# SCH_Cart_Main_PCB_2023-04-13.net
KiCad netlist of a schematic drawn in EasyEDA
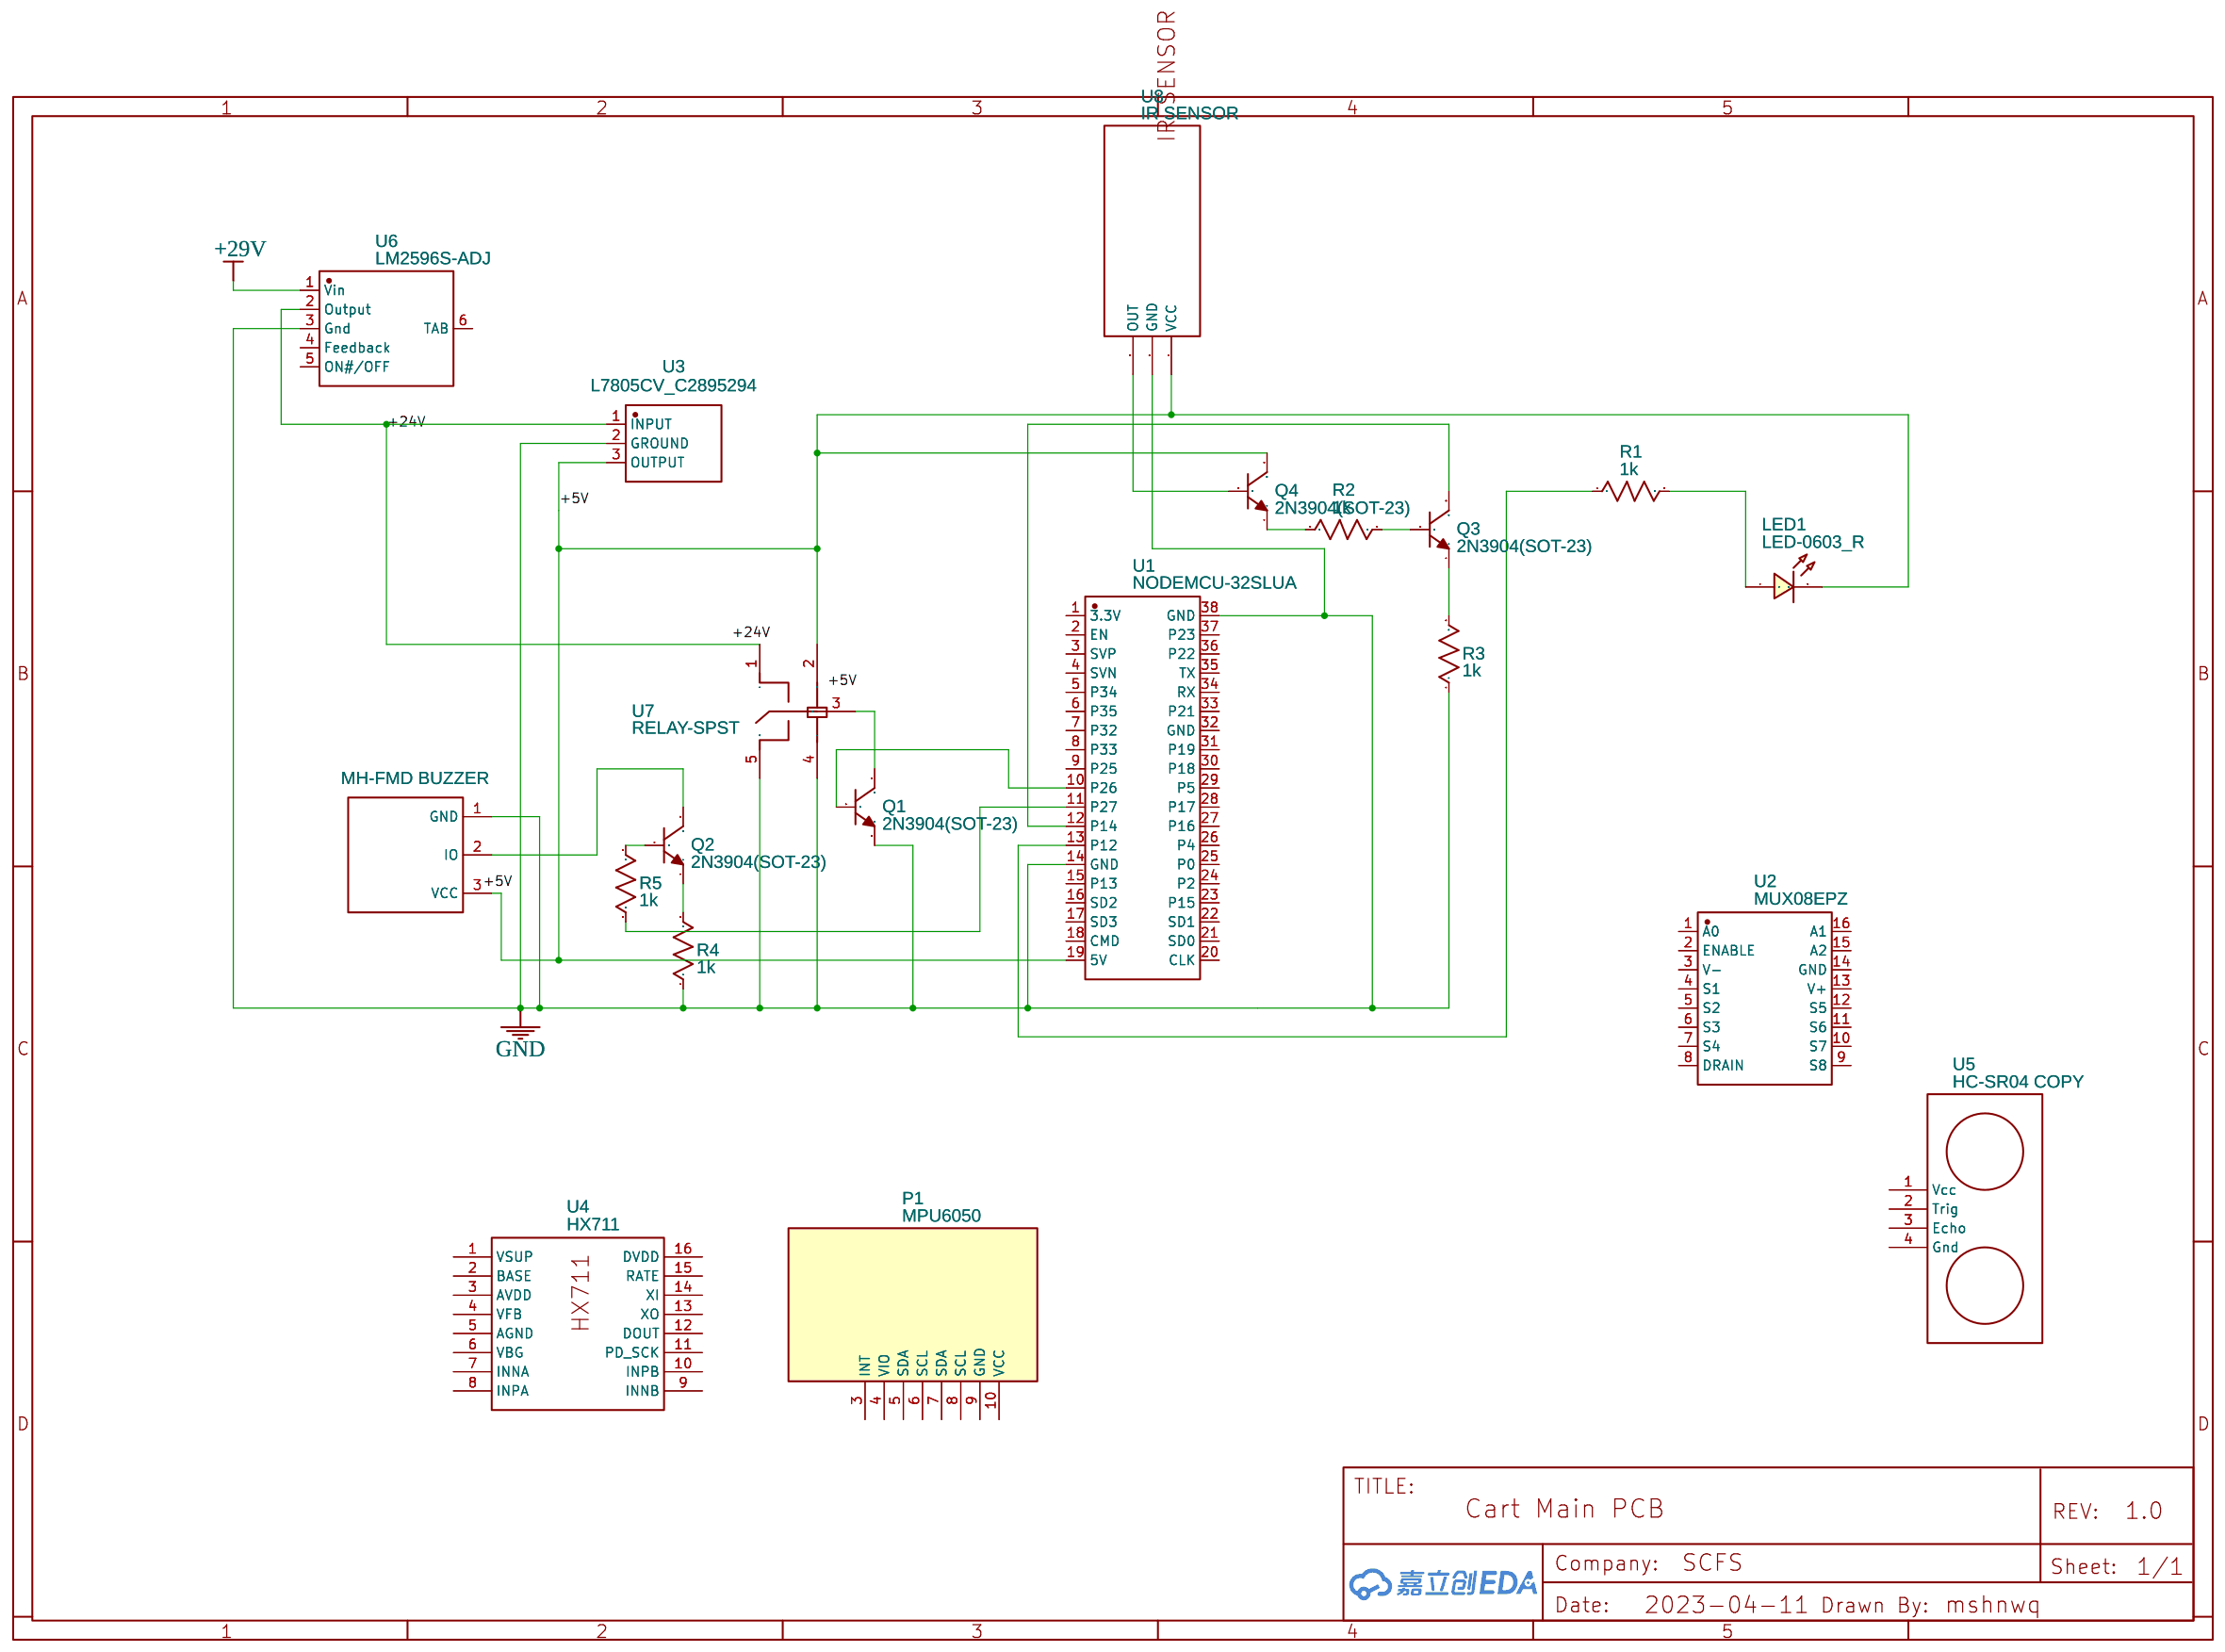
[diagram p0: schematic sheet]

(export (version "E")
  (design (tool "Eeschema 10.0.6"))
  (components
    (comp (ref "GND")
      (value "MH-FMD BUZZER")
      (fields (field (name "BOM_Supplier Part") "MH-FMD"))
      (libsource (lib "") (part "MH-FMD BUZZER"))
    )
    (comp (ref "LED1")
      (value "LED-0603_R")
      (fields
        (field (name "BOM_Manufacturer Part") "19-217/R6C-AL1M2VY/3T")
        (field (name "BOM_Supplier Part") "C72044")
      )
      (libsource (lib "") (part "LED-0603_R"))
    )
    (comp (ref "P1") (value "MPU6050") (libsource (lib "") (part "MPU6050")))
    (comp (ref "Q1")
      (value "2N3904(SOT-23)")
      (fields
        (field (name "BOM_Manufacturer Part") "2n3904S-RTK/PS")
        (field (name "BOM_Supplier Part") "C18536")
      )
      (libsource (lib "") (part "2N3904(SOT-23)"))
    )
    (comp (ref "Q2")
      (value "2N3904(SOT-23)")
      (fields
        (field (name "BOM_Manufacturer Part") "2n3904S-RTK/PS")
        (field (name "BOM_Supplier Part") "C18536")
      )
      (libsource (lib "") (part "2N3904(SOT-23)"))
    )
    (comp (ref "Q3")
      (value "2N3904(SOT-23)")
      (fields
        (field (name "BOM_Manufacturer Part") "2n3904S-RTK/PS")
        (field (name "BOM_Supplier Part") "C18536")
      )
      (libsource (lib "") (part "2N3904(SOT-23)"))
    )
    (comp (ref "Q4")
      (value "2N3904(SOT-23)")
      (fields
        (field (name "BOM_Manufacturer Part") "2n3904S-RTK/PS")
        (field (name "BOM_Supplier Part") "C18536")
      )
      (libsource (lib "") (part "2N3904(SOT-23)"))
    )
    (comp (ref "R1") (value "1k") (libsource (lib "") (part "R_0603_US_1")))
    (comp (ref "R2") (value "1k") (libsource (lib "") (part "R_0603_US_1")))
    (comp (ref "R3") (value "1k") (libsource (lib "") (part "R_0603_US")))
    (comp (ref "R4") (value "1k") (libsource (lib "") (part "R_0603_US")))
    (comp (ref "R5") (value "1k") (libsource (lib "") (part "R_0603_US_2")))
    (comp (ref "U1")
      (value "NODEMCU-32SLUA")
      (fields
        (field (name "BOM_Manufacturer Part") "NodeMCU-32SLua")
        (field (name "BOM_Supplier Part") "C111436")
      )
      (libsource (lib "") (part "NODEMCU-32SLUA"))
    )
    (comp (ref "U2")
      (value "MUX08EPZ")
      (fields (field (name "BOM_Supplier Part") "C690856"))
      (libsource (lib "") (part "MUX08EPZ"))
    )
    (comp (ref "U3")
      (value "L7805CV_C2895294")
      (fields
        (field (name "BOM_Manufacturer Part") "L7805CV带散热器")
        (field (name "BOM_Supplier Part") "C2895294")
      )
      (libsource (lib "") (part "L7805CV_C2895294"))
    )
    (comp (ref "U4")
      (value "HX711")
      (fields (field (name "BOM_Supplier Part") "C43656"))
      (libsource (lib "") (part "HX711"))
    )
    (comp (ref "U5") (value "HC-SR04 COPY") (libsource (lib "") (part "HC-SR04 COPY")))
    (comp (ref "U6")
      (value "LM2596S-ADJ")
      (fields (field (name "BOM_Supplier Part") "C347423"))
      (libsource (lib "") (part "LM2596S-ADJ"))
    )
    (comp (ref "U7")
      (value "RELAY-SPST")
      (fields
        (field (name "BOM_Manufacturer Part") "Relay-SPST")
        (field (name "BOM_Supplier Part") "C2941249")
      )
      (libsource (lib "") (part "RELAY-SPST"))
    )
    (comp (ref "U8") (value "IR SENSOR") (libsource (lib "") (part "MH-Sensor-Series Line Sensor")))
  )
  (nets
    (net (code "1") (name "+29V") (class "Default")
      (node (ref "U6") (pin "1") (pinfunction "Vin_1") (pintype "unspecified"))
    )
    (net (code "2") (name "/+5V") (class "Default")
      (node (ref "GND") (pin "3") (pinfunction "VCC_3") (pintype "unspecified"))
      (node (ref "LED1") (pin "2") (pinfunction "2_2") (pintype "unspecified"))
      (node (ref "Q4") (pin "3") (pinfunction "C_3") (pintype "input"))
      (node (ref "U1") (pin "19") (pinfunction "5V_19") (pintype "unspecified"))
      (node (ref "U3") (pin "3") (pinfunction "OUTPUT_3") (pintype "unspecified"))
      (node (ref "U7") (pin "2") (pinfunction "2_2") (pintype "unspecified"))
      (node (ref "U8") (pin "4") (pinfunction "VCC_4") (pintype "unspecified"))
    )
    (net (code "3") (name "/+24V") (class "Default")
      (node (ref "U3") (pin "1") (pinfunction "INPUT_1") (pintype "unspecified"))
      (node (ref "U6") (pin "2") (pinfunction "Output_2") (pintype "unspecified"))
      (node (ref "U7") (pin "1") (pinfunction "1_1") (pintype "unspecified"))
    )
    (net (code "4") (name "GND") (class "Default")
      (node (ref "GND") (pin "1") (pinfunction "GND_1") (pintype "unspecified"))
      (node (ref "Q1") (pin "1") (pinfunction "E_1") (pintype "input"))
      (node (ref "R3") (pin "1") (pinfunction "1_1") (pintype "unspecified"))
      (node (ref "R4") (pin "1") (pinfunction "1_1") (pintype "unspecified"))
      (node (ref "U1") (pin "14") (pinfunction "GND_14") (pintype "unspecified"))
      (node (ref "U1") (pin "38") (pinfunction "GND_38") (pintype "unspecified"))
      (node (ref "U3") (pin "2") (pinfunction "GROUND_2") (pintype "unspecified"))
      (node (ref "U6") (pin "3") (pinfunction "Gnd_3") (pintype "unspecified"))
      (node (ref "U7") (pin "4") (pinfunction "4_4") (pintype "unspecified"))
      (node (ref "U7") (pin "5") (pinfunction "5_5") (pintype "unspecified"))
      (node (ref "U8") (pin "3") (pinfunction "GND_3") (pintype "unspecified"))
    )
    (net (code "5") (name "Net-(GND-IO)") (class "Default")
      (node (ref "GND") (pin "2") (pinfunction "IO_2") (pintype "unspecified"))
      (node (ref "Q2") (pin "3") (pinfunction "C_3") (pintype "input"))
    )
    (net (code "6") (name "Net-(LED1-Pad1)") (class "Default")
      (node (ref "LED1") (pin "1") (pinfunction "1_1") (pintype "unspecified"))
      (node (ref "R1") (pin "2") (pinfunction "2_2") (pintype "unspecified"))
    )
    (net (code "7") (name "Net-(Q1-B)") (class "Default")
      (node (ref "Q1") (pin "2") (pinfunction "B_2") (pintype "input"))
      (node (ref "U1") (pin "10") (pinfunction "P26_10") (pintype "unspecified"))
    )
    (net (code "8") (name "Net-(Q1-C)") (class "Default")
      (node (ref "Q1") (pin "3") (pinfunction "C_3") (pintype "input"))
      (node (ref "U7") (pin "3") (pinfunction "3_3") (pintype "unspecified"))
    )
    (net (code "9") (name "Net-(Q2-B)") (class "Default")
      (node (ref "Q2") (pin "2") (pinfunction "B_2") (pintype "input"))
      (node (ref "R5") (pin "1") (pinfunction "1_1") (pintype "unspecified"))
    )
    (net (code "10") (name "Net-(Q2-E)") (class "Default")
      (node (ref "Q2") (pin "1") (pinfunction "E_1") (pintype "input"))
      (node (ref "R4") (pin "2") (pinfunction "2_2") (pintype "unspecified"))
    )
    (net (code "11") (name "Net-(Q3-B)") (class "Default")
      (node (ref "Q3") (pin "2") (pinfunction "B_2") (pintype "input"))
      (node (ref "R2") (pin "2") (pinfunction "2_2") (pintype "unspecified"))
    )
    (net (code "12") (name "Net-(Q3-C)") (class "Default")
      (node (ref "Q3") (pin "3") (pinfunction "C_3") (pintype "input"))
      (node (ref "U1") (pin "12") (pinfunction "P14_12") (pintype "unspecified"))
    )
    (net (code "13") (name "Net-(Q3-E)") (class "Default")
      (node (ref "Q3") (pin "1") (pinfunction "E_1") (pintype "input"))
      (node (ref "R3") (pin "2") (pinfunction "2_2") (pintype "unspecified"))
    )
    (net (code "14") (name "Net-(Q4-B)") (class "Default")
      (node (ref "Q4") (pin "2") (pinfunction "B_2") (pintype "input"))
      (node (ref "U8") (pin "2") (pinfunction "OUT_2") (pintype "unspecified"))
    )
    (net (code "15") (name "Net-(Q4-E)") (class "Default")
      (node (ref "Q4") (pin "1") (pinfunction "E_1") (pintype "input"))
      (node (ref "R2") (pin "1") (pinfunction "1_1") (pintype "unspecified"))
    )
    (net (code "16") (name "Net-(U1-P12)") (class "Default")
      (node (ref "R1") (pin "1") (pinfunction "1_1") (pintype "unspecified"))
      (node (ref "U1") (pin "13") (pinfunction "P12_13") (pintype "unspecified"))
    )
    (net (code "17") (name "Net-(U1-P27)") (class "Default")
      (node (ref "R5") (pin "2") (pinfunction "2_2") (pintype "unspecified"))
      (node (ref "U1") (pin "11") (pinfunction "P27_11") (pintype "unspecified"))
    )
    (net (code "18") (name "unconnected-(P1-GND-Pad9)") (class "Default")
      (node (ref "P1") (pin "9") (pinfunction "GND_9") (pintype "unspecified"))
    )
    (net (code "19") (name "unconnected-(P1-INT-Pad3)") (class "Default")
      (node (ref "P1") (pin "3") (pinfunction "INT_3") (pintype "unspecified"))
    )
    (net (code "20") (name "unconnected-(P1-SCL-Pad6)") (class "Default")
      (node (ref "P1") (pin "6") (pinfunction "SCL_6") (pintype "unspecified"))
    )
    (net (code "21") (name "unconnected-(P1-SCL-Pad8)") (class "Default")
      (node (ref "P1") (pin "8") (pinfunction "SCL_8") (pintype "unspecified"))
    )
    (net (code "22") (name "unconnected-(P1-SDA-Pad5)") (class "Default")
      (node (ref "P1") (pin "5") (pinfunction "SDA_5") (pintype "unspecified"))
    )
    (net (code "23") (name "unconnected-(P1-SDA-Pad7)") (class "Default")
      (node (ref "P1") (pin "7") (pinfunction "SDA_7") (pintype "unspecified"))
    )
    (net (code "24") (name "unconnected-(P1-VCC-Pad10)") (class "Default")
      (node (ref "P1") (pin "10") (pinfunction "VCC_10") (pintype "unspecified"))
    )
    (net (code "25") (name "unconnected-(P1-VIO-Pad4)") (class "Default")
      (node (ref "P1") (pin "4") (pinfunction "VIO_4") (pintype "unspecified"))
    )
    (net (code "26") (name "unconnected-(U1-3.3V-Pad1)") (class "Default")
      (node (ref "U1") (pin "1") (pinfunction "3.3V_1") (pintype "unspecified"))
    )
    (net (code "27") (name "unconnected-(U1-CLK-Pad20)") (class "Default")
      (node (ref "U1") (pin "20") (pinfunction "CLK_20") (pintype "unspecified"))
    )
    (net (code "28") (name "unconnected-(U1-CMD-Pad18)") (class "Default")
      (node (ref "U1") (pin "18") (pinfunction "CMD_18") (pintype "unspecified"))
    )
    (net (code "29") (name "unconnected-(U1-EN-Pad2)") (class "Default")
      (node (ref "U1") (pin "2") (pinfunction "EN_2") (pintype "unspecified"))
    )
    (net (code "30") (name "unconnected-(U1-GND-Pad32)") (class "Default")
      (node (ref "U1") (pin "32") (pinfunction "GND_32") (pintype "unspecified"))
    )
    (net (code "31") (name "unconnected-(U1-P0-Pad25)") (class "Default")
      (node (ref "U1") (pin "25") (pinfunction "P0_25") (pintype "unspecified"))
    )
    (net (code "32") (name "unconnected-(U1-P2-Pad24)") (class "Default")
      (node (ref "U1") (pin "24") (pinfunction "P2_24") (pintype "unspecified"))
    )
    (net (code "33") (name "unconnected-(U1-P4-Pad26)") (class "Default")
      (node (ref "U1") (pin "26") (pinfunction "P4_26") (pintype "unspecified"))
    )
    (net (code "34") (name "unconnected-(U1-P5-Pad29)") (class "Default")
      (node (ref "U1") (pin "29") (pinfunction "P5_29") (pintype "unspecified"))
    )
    (net (code "35") (name "unconnected-(U1-P13-Pad15)") (class "Default")
      (node (ref "U1") (pin "15") (pinfunction "P13_15") (pintype "unspecified"))
    )
    (net (code "36") (name "unconnected-(U1-P15-Pad23)") (class "Default")
      (node (ref "U1") (pin "23") (pinfunction "P15_23") (pintype "unspecified"))
    )
    (net (code "37") (name "unconnected-(U1-P16-Pad27)") (class "Default")
      (node (ref "U1") (pin "27") (pinfunction "P16_27") (pintype "unspecified"))
    )
    (net (code "38") (name "unconnected-(U1-P17-Pad28)") (class "Default")
      (node (ref "U1") (pin "28") (pinfunction "P17_28") (pintype "unspecified"))
    )
    (net (code "39") (name "unconnected-(U1-P18-Pad30)") (class "Default")
      (node (ref "U1") (pin "30") (pinfunction "P18_30") (pintype "unspecified"))
    )
    (net (code "40") (name "unconnected-(U1-P19-Pad31)") (class "Default")
      (node (ref "U1") (pin "31") (pinfunction "P19_31") (pintype "unspecified"))
    )
    (net (code "41") (name "unconnected-(U1-P21-Pad33)") (class "Default")
      (node (ref "U1") (pin "33") (pinfunction "P21_33") (pintype "unspecified"))
    )
    (net (code "42") (name "unconnected-(U1-P22-Pad36)") (class "Default")
      (node (ref "U1") (pin "36") (pinfunction "P22_36") (pintype "unspecified"))
    )
    (net (code "43") (name "unconnected-(U1-P23-Pad37)") (class "Default")
      (node (ref "U1") (pin "37") (pinfunction "P23_37") (pintype "unspecified"))
    )
    (net (code "44") (name "unconnected-(U1-P25-Pad9)") (class "Default")
      (node (ref "U1") (pin "9") (pinfunction "P25_9") (pintype "unspecified"))
    )
    (net (code "45") (name "unconnected-(U1-P32-Pad7)") (class "Default")
      (node (ref "U1") (pin "7") (pinfunction "P32_7") (pintype "unspecified"))
    )
    (net (code "46") (name "unconnected-(U1-P33-Pad8)") (class "Default")
      (node (ref "U1") (pin "8") (pinfunction "P33_8") (pintype "unspecified"))
    )
    (net (code "47") (name "unconnected-(U1-P34-Pad5)") (class "Default")
      (node (ref "U1") (pin "5") (pinfunction "P34_5") (pintype "unspecified"))
    )
    (net (code "48") (name "unconnected-(U1-P35-Pad6)") (class "Default")
      (node (ref "U1") (pin "6") (pinfunction "P35_6") (pintype "unspecified"))
    )
    (net (code "49") (name "unconnected-(U1-RX-Pad34)") (class "Default")
      (node (ref "U1") (pin "34") (pinfunction "RX_34") (pintype "unspecified"))
    )
    (net (code "50") (name "unconnected-(U1-SD0-Pad21)") (class "Default")
      (node (ref "U1") (pin "21") (pinfunction "SD0_21") (pintype "unspecified"))
    )
    (net (code "51") (name "unconnected-(U1-SD1-Pad22)") (class "Default")
      (node (ref "U1") (pin "22") (pinfunction "SD1_22") (pintype "unspecified"))
    )
    (net (code "52") (name "unconnected-(U1-SD2-Pad16)") (class "Default")
      (node (ref "U1") (pin "16") (pinfunction "SD2_16") (pintype "unspecified"))
    )
    (net (code "53") (name "unconnected-(U1-SD3-Pad17)") (class "Default")
      (node (ref "U1") (pin "17") (pinfunction "SD3_17") (pintype "unspecified"))
    )
    (net (code "54") (name "unconnected-(U1-SVN-Pad4)") (class "Default")
      (node (ref "U1") (pin "4") (pinfunction "SVN_4") (pintype "unspecified"))
    )
    (net (code "55") (name "unconnected-(U1-SVP-Pad3)") (class "Default")
      (node (ref "U1") (pin "3") (pinfunction "SVP_3") (pintype "unspecified"))
    )
    (net (code "56") (name "unconnected-(U1-TX-Pad35)") (class "Default")
      (node (ref "U1") (pin "35") (pinfunction "TX_35") (pintype "unspecified"))
    )
    (net (code "57") (name "unconnected-(U2-A0-Pad1)") (class "Default")
      (node (ref "U2") (pin "1") (pinfunction "A0_1") (pintype "unspecified"))
    )
    (net (code "58") (name "unconnected-(U2-A1-Pad16)") (class "Default")
      (node (ref "U2") (pin "16") (pinfunction "A1_16") (pintype "unspecified"))
    )
    (net (code "59") (name "unconnected-(U2-A2-Pad15)") (class "Default")
      (node (ref "U2") (pin "15") (pinfunction "A2_15") (pintype "unspecified"))
    )
    (net (code "60") (name "unconnected-(U2-DRAIN-Pad8)") (class "Default")
      (node (ref "U2") (pin "8") (pinfunction "DRAIN_8") (pintype "unspecified"))
    )
    (net (code "61") (name "unconnected-(U2-ENABLE-Pad2)") (class "Default")
      (node (ref "U2") (pin "2") (pinfunction "ENABLE_2") (pintype "unspecified"))
    )
    (net (code "62") (name "unconnected-(U2-GND-Pad14)") (class "Default")
      (node (ref "U2") (pin "14") (pinfunction "GND_14") (pintype "unspecified"))
    )
    (net (code "63") (name "unconnected-(U2-S1-Pad4)") (class "Default")
      (node (ref "U2") (pin "4") (pinfunction "S1_4") (pintype "unspecified"))
    )
    (net (code "64") (name "unconnected-(U2-S2-Pad5)") (class "Default")
      (node (ref "U2") (pin "5") (pinfunction "S2_5") (pintype "unspecified"))
    )
    (net (code "65") (name "unconnected-(U2-S3-Pad6)") (class "Default")
      (node (ref "U2") (pin "6") (pinfunction "S3_6") (pintype "unspecified"))
    )
    (net (code "66") (name "unconnected-(U2-S4-Pad7)") (class "Default")
      (node (ref "U2") (pin "7") (pinfunction "S4_7") (pintype "unspecified"))
    )
    (net (code "67") (name "unconnected-(U2-S5-Pad12)") (class "Default")
      (node (ref "U2") (pin "12") (pinfunction "S5_12") (pintype "unspecified"))
    )
    (net (code "68") (name "unconnected-(U2-S6-Pad11)") (class "Default")
      (node (ref "U2") (pin "11") (pinfunction "S6_11") (pintype "unspecified"))
    )
    (net (code "69") (name "unconnected-(U2-S7-Pad10)") (class "Default")
      (node (ref "U2") (pin "10") (pinfunction "S7_10") (pintype "unspecified"))
    )
    (net (code "70") (name "unconnected-(U2-S8-Pad9)") (class "Default")
      (node (ref "U2") (pin "9") (pinfunction "S8_9") (pintype "unspecified"))
    )
    (net (code "71") (name "unconnected-(U2-V+-Pad13)") (class "Default")
      (node (ref "U2") (pin "13") (pinfunction "V+_13") (pintype "unspecified"))
    )
    (net (code "72") (name "unconnected-(U2-V--Pad3)") (class "Default")
      (node (ref "U2") (pin "3") (pinfunction "V-_3") (pintype "unspecified"))
    )
    (net (code "73") (name "unconnected-(U4-AGND-Pad5)") (class "Default")
      (node (ref "U4") (pin "5") (pinfunction "AGND_5") (pintype "unspecified"))
    )
    (net (code "74") (name "unconnected-(U4-AVDD-Pad3)") (class "Default")
      (node (ref "U4") (pin "3") (pinfunction "AVDD_3") (pintype "unspecified"))
    )
    (net (code "75") (name "unconnected-(U4-BASE-Pad2)") (class "Default")
      (node (ref "U4") (pin "2") (pinfunction "BASE_2") (pintype "unspecified"))
    )
    (net (code "76") (name "unconnected-(U4-DOUT-Pad12)") (class "Default")
      (node (ref "U4") (pin "12") (pinfunction "DOUT_12") (pintype "unspecified"))
    )
    (net (code "77") (name "unconnected-(U4-DVDD-Pad16)") (class "Default")
      (node (ref "U4") (pin "16") (pinfunction "DVDD_16") (pintype "unspecified"))
    )
    (net (code "78") (name "unconnected-(U4-INNA-Pad7)") (class "Default")
      (node (ref "U4") (pin "7") (pinfunction "INNA_7") (pintype "unspecified"))
    )
    (net (code "79") (name "unconnected-(U4-INNB-Pad9)") (class "Default")
      (node (ref "U4") (pin "9") (pinfunction "INNB_9") (pintype "unspecified"))
    )
    (net (code "80") (name "unconnected-(U4-INPA-Pad8)") (class "Default")
      (node (ref "U4") (pin "8") (pinfunction "INPA_8") (pintype "unspecified"))
    )
    (net (code "81") (name "unconnected-(U4-INPB-Pad10)") (class "Default")
      (node (ref "U4") (pin "10") (pinfunction "INPB_10") (pintype "unspecified"))
    )
    (net (code "82") (name "unconnected-(U4-PD_SCK-Pad11)") (class "Default")
      (node (ref "U4") (pin "11") (pinfunction "PD_SCK_11") (pintype "unspecified"))
    )
    (net (code "83") (name "unconnected-(U4-RATE-Pad15)") (class "Default")
      (node (ref "U4") (pin "15") (pinfunction "RATE_15") (pintype "unspecified"))
    )
    (net (code "84") (name "unconnected-(U4-VBG-Pad6)") (class "Default")
      (node (ref "U4") (pin "6") (pinfunction "VBG_6") (pintype "unspecified"))
    )
    (net (code "85") (name "unconnected-(U4-VFB-Pad4)") (class "Default")
      (node (ref "U4") (pin "4") (pinfunction "VFB_4") (pintype "unspecified"))
    )
    (net (code "86") (name "unconnected-(U4-VSUP-Pad1)") (class "Default")
      (node (ref "U4") (pin "1") (pinfunction "VSUP_1") (pintype "unspecified"))
    )
    (net (code "87") (name "unconnected-(U4-XI-Pad14)") (class "Default")
      (node (ref "U4") (pin "14") (pinfunction "XI_14") (pintype "unspecified"))
    )
    (net (code "88") (name "unconnected-(U4-XO-Pad13)") (class "Default")
      (node (ref "U4") (pin "13") (pinfunction "XO_13") (pintype "unspecified"))
    )
    (net (code "89") (name "unconnected-(U5-Echo-Pad3)") (class "Default")
      (node (ref "U5") (pin "3") (pinfunction "Echo_3") (pintype "unspecified"))
    )
    (net (code "90") (name "unconnected-(U5-Gnd-Pad4)") (class "Default")
      (node (ref "U5") (pin "4") (pinfunction "Gnd_4") (pintype "unspecified"))
    )
    (net (code "91") (name "unconnected-(U5-Trig-Pad2)") (class "Default")
      (node (ref "U5") (pin "2") (pinfunction "Trig_2") (pintype "unspecified"))
    )
    (net (code "92") (name "unconnected-(U5-Vcc-Pad1)") (class "Default")
      (node (ref "U5") (pin "1") (pinfunction "Vcc_1") (pintype "unspecified"))
    )
    (net (code "93") (name "unconnected-(U6-Feedback-Pad4)") (class "Default")
      (node (ref "U6") (pin "4") (pinfunction "Feedback_4") (pintype "unspecified"))
    )
    (net (code "94") (name "unconnected-(U6-ON#{slash}OFF-Pad5)") (class "Default")
      (node (ref "U6") (pin "5") (pinfunction "ON#/OFF_5") (pintype "unspecified"))
    )
    (net (code "95") (name "unconnected-(U6-TAB-Pad6)") (class "Default")
      (node (ref "U6") (pin "6") (pinfunction "TAB_6") (pintype "unspecified"))
    )
  )
)
